# MPPT_V1_0_1_5V_Supply.net
KiCad netlist of a schematic drawn in Altium Designer
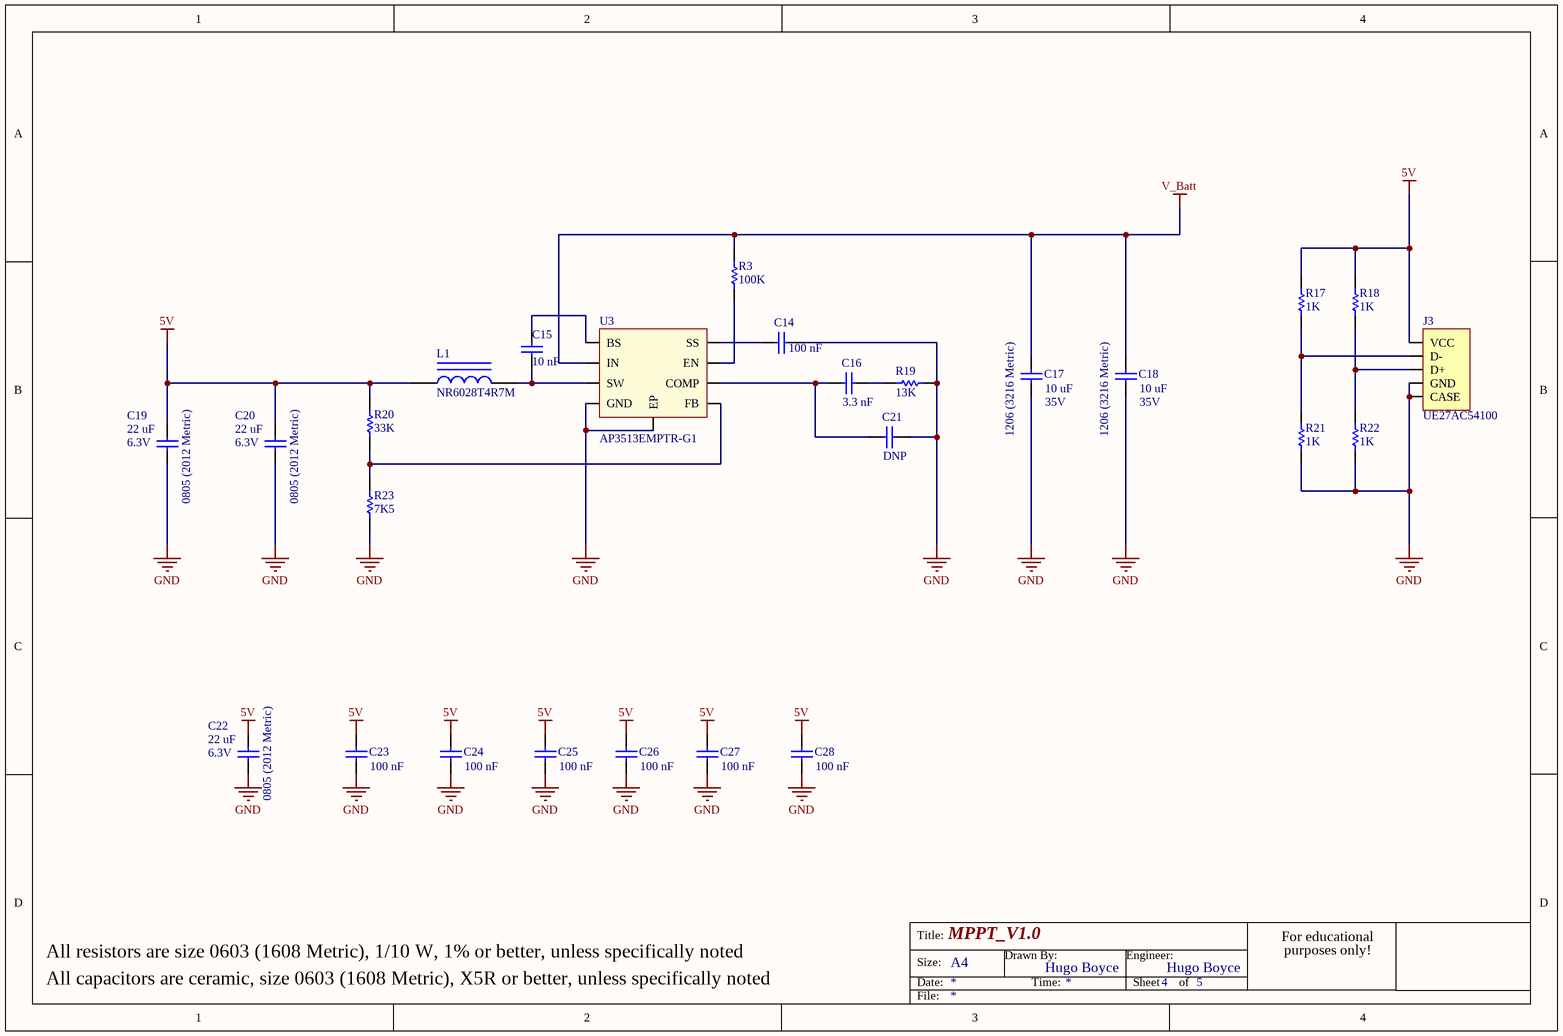
[diagram p0: MPPT_V1.0.1_5V_Supply.SchDoc]

(export (version "E")
  (design (tool "Eeschema 10.0.6"))
  (components
    (comp (ref "C14")
      (value "100 nF")
      (footprint "CAPC1608N")
      (description "Capacitor")
      (fields (field (name "Comment") "Cap SMD") (field (name "PUBLISHER") "Altium Limited"))
      (libsource (lib "Miscellaneous Devices") (part "Cap SMD"))
    )
    (comp (ref "C15")
      (value "10 nF")
      (footprint "CAPC1608N")
      (description "Capacitor")
      (fields (field (name "Comment") "1608") (field (name "PUBLISHER") "Altium Limited"))
      (libsource (lib "Miscellaneous Devices") (part "Cap SMD"))
    )
    (comp (ref "C16")
      (value "3.3 nF")
      (footprint "CAPC1608N")
      (description "Capacitor")
      (fields (field (name "Comment") "Cap SMD") (field (name "PUBLISHER") "Altium Limited"))
      (libsource (lib "Miscellaneous Devices") (part "Cap SMD"))
    )
    (comp (ref "C17")
      (value "10 uF")
      (footprint "CAPC3216N")
      (description "Capacitor")
      (fields
        (field (name "SIZE") "1206 (3216 Metric)")
        (field (name "VOLTAGE RATING") "35V")
        (field (name "Comment") "Cap SMD")
        (field (name "PUBLISHER") "Altium Limited")
      )
      (libsource (lib "Miscellaneous Devices") (part "Cap SMD"))
    )
    (comp (ref "C18")
      (value "10 uF")
      (footprint "CAPC3216N")
      (description "Capacitor")
      (fields
        (field (name "SIZE") "1206 (3216 Metric)")
        (field (name "VOLTAGE RATING") "35V")
        (field (name "Comment") "Cap SMD")
        (field (name "PUBLISHER") "Altium Limited")
      )
      (libsource (lib "Miscellaneous Devices") (part "Cap SMD"))
    )
    (comp (ref "C19")
      (value "22 uF")
      (footprint "CAPC2012N")
      (description "Capacitor")
      (fields
        (field (name "SIZE") "0805 (2012 Metric)")
        (field (name "VOLTAGE RATING") "6.3V")
        (field (name "Comment") "JMK212BBJ226MGHT")
        (field (name "PUBLISHER") "Altium Limited")
      )
      (libsource (lib "Miscellaneous Devices") (part "Cap SMD"))
    )
    (comp (ref "C20")
      (value "22 uF")
      (footprint "CAPC2012N")
      (description "Capacitor")
      (fields
        (field (name "SIZE") "0805 (2012 Metric)")
        (field (name "VOLTAGE RATING") "6.3V")
        (field (name "Comment") "JMK212BBJ226MGHT")
        (field (name "PUBLISHER") "Altium Limited")
      )
      (libsource (lib "Miscellaneous Devices") (part "Cap SMD"))
    )
    (comp (ref "C21")
      (value "DNP")
      (footprint "CAPC1608N")
      (description "Capacitor")
      (fields (field (name "Comment") "Cap SMD") (field (name "PUBLISHER") "Altium Limited"))
      (libsource (lib "Miscellaneous Devices") (part "Cap SMD"))
    )
    (comp (ref "C22")
      (value "22 uF")
      (footprint "CAPC2012N")
      (description "Capacitor")
      (fields
        (field (name "SIZE") "0805 (2012 Metric)")
        (field (name "VOLTAGE RATING") "6.3V")
        (field (name "Comment") "JMK212BBJ226MGHT")
        (field (name "PUBLISHER") "Altium Limited")
      )
      (libsource (lib "Miscellaneous Devices") (part "Cap SMD"))
    )
    (comp (ref "C23")
      (value "100 nF")
      (footprint "CAPC1608N")
      (description "Capacitor")
      (fields (field (name "Comment") "Cap SMD") (field (name "PUBLISHER") "Altium Limited"))
      (libsource (lib "Miscellaneous Devices") (part "Cap SMD"))
    )
    (comp (ref "C24")
      (value "100 nF")
      (footprint "CAPC1608N")
      (description "Capacitor")
      (fields (field (name "Comment") "Cap SMD") (field (name "PUBLISHER") "Altium Limited"))
      (libsource (lib "Miscellaneous Devices") (part "Cap SMD"))
    )
    (comp (ref "C25")
      (value "100 nF")
      (footprint "CAPC1608N")
      (description "Capacitor")
      (fields (field (name "Comment") "Cap SMD") (field (name "PUBLISHER") "Altium Limited"))
      (libsource (lib "Miscellaneous Devices") (part "Cap SMD"))
    )
    (comp (ref "C26")
      (value "100 nF")
      (footprint "CAPC1608N")
      (description "Capacitor")
      (fields (field (name "Comment") "Cap SMD") (field (name "PUBLISHER") "Altium Limited"))
      (libsource (lib "Miscellaneous Devices") (part "Cap SMD"))
    )
    (comp (ref "C27")
      (value "100 nF")
      (footprint "CAPC1608N")
      (description "Capacitor")
      (fields (field (name "Comment") "Cap SMD") (field (name "PUBLISHER") "Altium Limited"))
      (libsource (lib "Miscellaneous Devices") (part "Cap SMD"))
    )
    (comp (ref "C28")
      (value "100 nF")
      (footprint "CAPC1608N")
      (description "Capacitor")
      (fields (field (name "Comment") "Cap SMD") (field (name "PUBLISHER") "Altium Limited"))
      (libsource (lib "Miscellaneous Devices") (part "Cap SMD"))
    )
    (comp (ref "J3")
      (value "UE27AC54100")
      (footprint "UE27AC5410")
      (description "CONN RCPT USB TYPE A R/A GOLD")
      (fields
        (field (name "MANUFACTURER") "Amphenol Commercial Products")
        (field (name "MANUFACTURER PART NUMBER") "UE27AC54100")
      )
      (libsource (lib "MPPT_SCH_Library") (part "UE27AC54100"))
    )
    (comp (ref "L1")
      (value "NR6028T4R7M")
      (footprint "NR6028")
      (description "FIXED IND 4.7UH 3A 40.3 MOHM SMD")
      (fields
        (field (name "MANUFACTURER") "Taiyo Yuden")
        (field (name "TOLERANCE") "±20%")
        (field (name "MANUFACTURER PART NUMBER") "NR6028T4R7M")
      )
      (libsource (lib "MPPT_SCH_Library") (part "NR6028T4R7M"))
    )
    (comp (ref "R3")
      (value "100K")
      (footprint "RESC1608N")
      (description "Resistor")
      (fields (field (name "Comment") "Res SMD") (field (name "PUBLISHER") "Altium Limited"))
      (libsource (lib "Miscellaneous Devices") (part "Res SMD"))
    )
    (comp (ref "R17")
      (value "1K")
      (footprint "RESC1608N")
      (description "Resistor")
      (fields (field (name "Comment") "Res SMD") (field (name "PUBLISHER") "Altium Limited"))
      (libsource (lib "Miscellaneous Devices") (part "Res SMD"))
    )
    (comp (ref "R18")
      (value "1K")
      (footprint "RESC1608N")
      (description "Resistor")
      (fields (field (name "Comment") "Res SMD") (field (name "PUBLISHER") "Altium Limited"))
      (libsource (lib "Miscellaneous Devices") (part "Res SMD"))
    )
    (comp (ref "R19")
      (value "13K")
      (footprint "RESC1608N")
      (description "Resistor")
      (fields (field (name "Comment") "Res SMD") (field (name "PUBLISHER") "Altium Limited"))
      (libsource (lib "Miscellaneous Devices") (part "Res SMD"))
    )
    (comp (ref "R20")
      (value "33K")
      (footprint "RESC1608N")
      (description "Resistor")
      (fields (field (name "Comment") "Res SMD") (field (name "PUBLISHER") "Altium Limited"))
      (libsource (lib "Miscellaneous Devices") (part "Res SMD"))
    )
    (comp (ref "R21")
      (value "1K")
      (footprint "RESC1608N")
      (description "Resistor")
      (fields (field (name "Comment") "Res SMD") (field (name "PUBLISHER") "Altium Limited"))
      (libsource (lib "Miscellaneous Devices") (part "Res SMD"))
    )
    (comp (ref "R22")
      (value "1K")
      (footprint "RESC1608N")
      (description "Resistor")
      (fields (field (name "Comment") "Res SMD") (field (name "PUBLISHER") "Altium Limited"))
      (libsource (lib "Miscellaneous Devices") (part "Res SMD"))
    )
    (comp (ref "R23")
      (value "7K5")
      (footprint "RESC1608N")
      (description "Resistor")
      (fields (field (name "Comment") "Res SMD") (field (name "PUBLISHER") "Altium Limited"))
      (libsource (lib "Miscellaneous Devices") (part "Res SMD"))
    )
    (comp (ref "U3")
      (value "AP3513EMPTR-G1")
      (footprint "AP3513E")
      (description "IC REG BUCK ADJ 3A SYNC 8SOIC")
      (fields
        (field (name "MANUFACTURER") "Diodes Incorporated")
        (field (name "MANUFACTURER PART NUMBER") "AP3513EMPTR-G1")
      )
      (libsource (lib "MPPT_SCH_Library") (part "AP3513EMPTR-G1"))
    )
  )
  (nets
    (net (code "1") (name "5V") (class "Default")
      (node (ref "C19") (pin "2") (pinfunction "2_2") (pintype "passive"))
      (node (ref "C20") (pin "2") (pinfunction "2_2") (pintype "passive"))
      (node (ref "C22") (pin "2") (pinfunction "2_2") (pintype "passive"))
      (node (ref "C23") (pin "2") (pinfunction "2_2") (pintype "passive"))
      (node (ref "C24") (pin "2") (pinfunction "2_2") (pintype "passive"))
      (node (ref "C25") (pin "2") (pinfunction "2_2") (pintype "passive"))
      (node (ref "C26") (pin "2") (pinfunction "2_2") (pintype "passive"))
      (node (ref "C27") (pin "2") (pinfunction "2_2") (pintype "passive"))
      (node (ref "C28") (pin "2") (pinfunction "2_2") (pintype "passive"))
      (node (ref "J3") (pin "1") (pinfunction "VCC_1") (pintype "passive"))
      (node (ref "L1") (pin "1") (pinfunction "1_1") (pintype "passive"))
      (node (ref "R17") (pin "2") (pinfunction "2_2") (pintype "passive"))
      (node (ref "R18") (pin "2") (pinfunction "2_2") (pintype "passive"))
      (node (ref "R20") (pin "2") (pinfunction "2_2") (pintype "passive"))
    )
    (net (code "2") (name "GND") (class "Default")
      (node (ref "C14") (pin "2") (pinfunction "2_2") (pintype "passive"))
      (node (ref "C17") (pin "1") (pinfunction "1_1") (pintype "passive"))
      (node (ref "C18") (pin "1") (pinfunction "1_1") (pintype "passive"))
      (node (ref "C19") (pin "1") (pinfunction "1_1") (pintype "passive"))
      (node (ref "C20") (pin "1") (pinfunction "1_1") (pintype "passive"))
      (node (ref "C21") (pin "2") (pinfunction "2_2") (pintype "passive"))
      (node (ref "C22") (pin "1") (pinfunction "1_1") (pintype "passive"))
      (node (ref "C23") (pin "1") (pinfunction "1_1") (pintype "passive"))
      (node (ref "C24") (pin "1") (pinfunction "1_1") (pintype "passive"))
      (node (ref "C25") (pin "1") (pinfunction "1_1") (pintype "passive"))
      (node (ref "C26") (pin "1") (pinfunction "1_1") (pintype "passive"))
      (node (ref "C27") (pin "1") (pinfunction "1_1") (pintype "passive"))
      (node (ref "C28") (pin "1") (pinfunction "1_1") (pintype "passive"))
      (node (ref "J3") (pin "4") (pinfunction "GND_4") (pintype "passive"))
      (node (ref "J3") (pin "5") (pinfunction "CASE_5") (pintype "passive"))
      (node (ref "R19") (pin "2") (pinfunction "2_2") (pintype "passive"))
      (node (ref "R21") (pin "1") (pinfunction "1_1") (pintype "passive"))
      (node (ref "R22") (pin "1") (pinfunction "1_1") (pintype "passive"))
      (node (ref "R23") (pin "1") (pinfunction "1_1") (pintype "passive"))
      (node (ref "U3") (pin "4") (pinfunction "GND_4") (pintype "passive"))
      (node (ref "U3") (pin "9") (pinfunction "EP_9") (pintype "passive"))
    )
    (net (code "3") (name "Net-(C16-Pad2)") (class "Default")
      (node (ref "C16") (pin "2") (pinfunction "2_2") (pintype "passive"))
      (node (ref "R19") (pin "1") (pinfunction "1_1") (pintype "passive"))
    )
    (net (code "4") (name "Net-(J3-D+)") (class "Default")
      (node (ref "J3") (pin "3") (pinfunction "D+_3") (pintype "passive"))
      (node (ref "R18") (pin "1") (pinfunction "1_1") (pintype "passive"))
      (node (ref "R22") (pin "2") (pinfunction "2_2") (pintype "passive"))
    )
    (net (code "5") (name "Net-(J3-D-)") (class "Default")
      (node (ref "J3") (pin "2") (pinfunction "D-_2") (pintype "passive"))
      (node (ref "R17") (pin "1") (pinfunction "1_1") (pintype "passive"))
      (node (ref "R21") (pin "2") (pinfunction "2_2") (pintype "passive"))
    )
    (net (code "6") (name "Net-(U3-BS)") (class "Default")
      (node (ref "C15") (pin "2") (pinfunction "2_2") (pintype "passive"))
      (node (ref "U3") (pin "1") (pinfunction "BS_1") (pintype "passive"))
    )
    (net (code "7") (name "Net-(U3-COMP)") (class "Default")
      (node (ref "C16") (pin "1") (pinfunction "1_1") (pintype "passive"))
      (node (ref "C21") (pin "1") (pinfunction "1_1") (pintype "passive"))
      (node (ref "U3") (pin "6") (pinfunction "COMP_6") (pintype "passive"))
    )
    (net (code "8") (name "Net-(U3-EN)") (class "Default")
      (node (ref "R3") (pin "1") (pinfunction "1_1") (pintype "passive"))
      (node (ref "U3") (pin "7") (pinfunction "EN_7") (pintype "passive"))
    )
    (net (code "9") (name "Net-(U3-FB)") (class "Default")
      (node (ref "R20") (pin "1") (pinfunction "1_1") (pintype "passive"))
      (node (ref "R23") (pin "2") (pinfunction "2_2") (pintype "passive"))
      (node (ref "U3") (pin "5") (pinfunction "FB_5") (pintype "passive"))
    )
    (net (code "10") (name "Net-(U3-SS)") (class "Default")
      (node (ref "C14") (pin "1") (pinfunction "1_1") (pintype "passive"))
      (node (ref "U3") (pin "8") (pinfunction "SS_8") (pintype "passive"))
    )
    (net (code "11") (name "Net-(U3-SW)") (class "Default")
      (node (ref "C15") (pin "1") (pinfunction "1_1") (pintype "passive"))
      (node (ref "L1") (pin "2") (pinfunction "2_2") (pintype "passive"))
      (node (ref "U3") (pin "3") (pinfunction "SW_3") (pintype "passive"))
    )
    (net (code "12") (name "V_Batt") (class "Default")
      (node (ref "C17") (pin "2") (pinfunction "2_2") (pintype "passive"))
      (node (ref "C18") (pin "2") (pinfunction "2_2") (pintype "passive"))
      (node (ref "R3") (pin "2") (pinfunction "2_2") (pintype "passive"))
      (node (ref "U3") (pin "2") (pinfunction "IN_2") (pintype "passive"))
    )
  )
)
